# TripleCtrl_v2.net
KiCad netlist of a schematic drawn in EAGLE
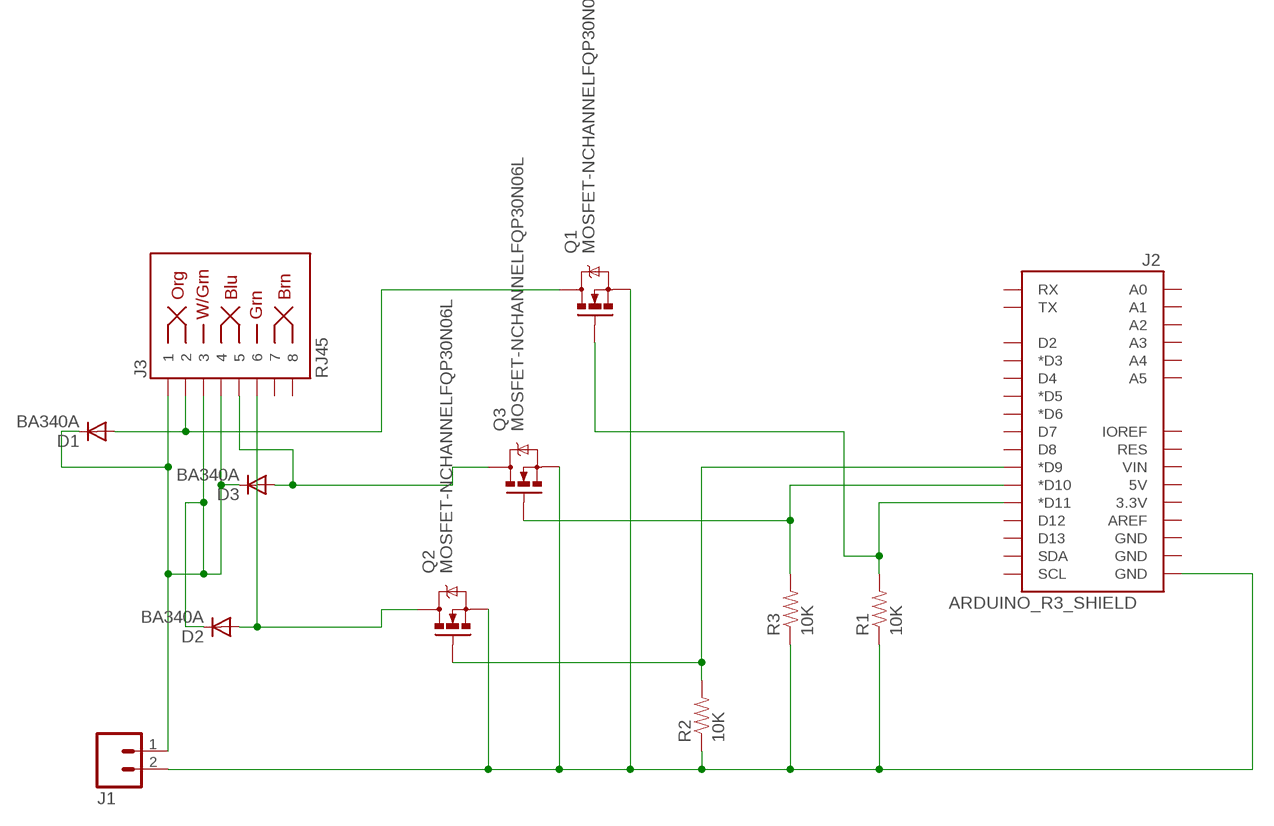
[diagram p0: schematic, sheet 1]

(export (version "E")
  (design (tool "Eeschema 10.0.6"))
  (components
    (comp (ref "D1")
      (value "BA340A")
      (footprint "eagle-import:DO41-10")
      (libsource (lib "eagle-import") (part "1N4004"))
    )
    (comp (ref "D2")
      (value "BA340A")
      (footprint "eagle-import:DO41-10")
      (libsource (lib "eagle-import") (part "1N4004"))
    )
    (comp (ref "D3")
      (value "BA340A")
      (footprint "eagle-import:DO41-10")
      (libsource (lib "eagle-import") (part "1N4004"))
    )
    (comp (ref "J1")
      (value "M025MM")
      (footprint "eagle-import:SCREWTERMINAL-5MM-2")
      (libsource (lib "eagle-import") (part "M025MM"))
    )
    (comp (ref "J2")
      (value "ARDUINO_R3_SHIELD")
      (footprint "eagle-import:UNO_R3_SHIELD")
      (libsource (lib "eagle-import") (part "ARDUINO_R3_SHIELD"))
    )
    (comp (ref "J3")
      (value "RJ45")
      (footprint "eagle-import:RJ45-8")
      (libsource (lib "eagle-import") (part "RJ45-8PTH"))
    )
    (comp (ref "Q1")
      (value "MOSFET-NCHANNELFQP30N06L")
      (footprint "eagle-import:TO220V")
      (libsource (lib "eagle-import") (part "MOSFET-NCHANNELFQP30N06L"))
    )
    (comp (ref "Q2")
      (value "MOSFET-NCHANNELFQP30N06L")
      (footprint "eagle-import:TO220V")
      (libsource (lib "eagle-import") (part "MOSFET-NCHANNELFQP30N06L"))
    )
    (comp (ref "Q3")
      (value "MOSFET-NCHANNELFQP30N06L")
      (footprint "eagle-import:TO220V")
      (libsource (lib "eagle-import") (part "MOSFET-NCHANNELFQP30N06L"))
    )
    (comp (ref "R1")
      (value "10K")
      (footprint "eagle-import:AXIAL-0.3-KIT")
      (libsource (lib "eagle-import") (part "10KOHM-1/6W-5%(PTH)KIT"))
    )
    (comp (ref "R2")
      (value "10K")
      (footprint "eagle-import:AXIAL-0.3-KIT")
      (libsource (lib "eagle-import") (part "10KOHM-1/6W-5%(PTH)KIT"))
    )
    (comp (ref "R3")
      (value "10K")
      (footprint "eagle-import:AXIAL-0.3-KIT")
      (libsource (lib "eagle-import") (part "10KOHM-1/6W-5%(PTH)KIT"))
    )
  )
  (nets
    (net (code "1") (name "Net-(D1-PadC)") (class "Default")
      (node (ref "D1") (pin "C") (pinfunction "C_C") (pintype "passive"))
      (node (ref "D2") (pin "C") (pinfunction "C_C") (pintype "passive"))
      (node (ref "D3") (pin "C") (pinfunction "C_C") (pintype "passive"))
      (node (ref "J1") (pin "1") (pinfunction "1_1") (pintype "passive"))
      (node (ref "J3") (pin "1") (pinfunction "1_1") (pintype "bidirectional"))
      (node (ref "J3") (pin "3") (pinfunction "3_3") (pintype "bidirectional"))
      (node (ref "J3") (pin "4") (pinfunction "4_4") (pintype "bidirectional"))
    )
    (net (code "2") (name "Net-(J2-*D9)") (class "Default")
      (node (ref "J2") (pin "D9") (pinfunction "*D9_D9") (pintype "bidirectional"))
      (node (ref "Q2") (pin "1") (pinfunction "G_1") (pintype "passive"))
      (node (ref "R2") (pin "P$2") (pinfunction "2_P$2") (pintype "passive"))
    )
    (net (code "3") (name "Net-(J2-*D10)") (class "Default")
      (node (ref "J2") (pin "D10") (pinfunction "*D10_D10") (pintype "bidirectional"))
      (node (ref "Q3") (pin "1") (pinfunction "G_1") (pintype "passive"))
      (node (ref "R3") (pin "P$2") (pinfunction "2_P$2") (pintype "passive"))
    )
    (net (code "4") (name "Net-(J2-*D11)") (class "Default")
      (node (ref "J2") (pin "D11") (pinfunction "*D11_D11") (pintype "bidirectional"))
      (node (ref "Q1") (pin "1") (pinfunction "G_1") (pintype "passive"))
      (node (ref "R1") (pin "P$2") (pinfunction "2_P$2") (pintype "passive"))
    )
    (net (code "5") (name "Net-(Q1-D)") (class "Default")
      (node (ref "D1") (pin "A") (pinfunction "A_A") (pintype "passive"))
      (node (ref "J3") (pin "2") (pinfunction "2_2") (pintype "bidirectional"))
      (node (ref "Q1") (pin "2") (pinfunction "D_2") (pintype "passive"))
    )
    (net (code "6") (name "Net-(Q1-S)") (class "Default")
      (node (ref "J1") (pin "2") (pinfunction "2_2") (pintype "passive"))
      (node (ref "J2") (pin "GND@0") (pinfunction "GND_GND@0") (pintype "bidirectional"))
      (node (ref "Q1") (pin "3") (pinfunction "S_3") (pintype "passive"))
      (node (ref "Q2") (pin "3") (pinfunction "S_3") (pintype "passive"))
      (node (ref "Q3") (pin "3") (pinfunction "S_3") (pintype "passive"))
      (node (ref "R1") (pin "P$1") (pinfunction "1_P$1") (pintype "passive"))
      (node (ref "R2") (pin "P$1") (pinfunction "1_P$1") (pintype "passive"))
      (node (ref "R3") (pin "P$1") (pinfunction "1_P$1") (pintype "passive"))
    )
    (net (code "7") (name "Net-(Q2-D)") (class "Default")
      (node (ref "D2") (pin "A") (pinfunction "A_A") (pintype "passive"))
      (node (ref "J3") (pin "6") (pinfunction "6_6") (pintype "bidirectional"))
      (node (ref "Q2") (pin "2") (pinfunction "D_2") (pintype "passive"))
    )
    (net (code "8") (name "Net-(Q3-D)") (class "Default")
      (node (ref "D3") (pin "A") (pinfunction "A_A") (pintype "passive"))
      (node (ref "J3") (pin "5") (pinfunction "5_5") (pintype "bidirectional"))
      (node (ref "Q3") (pin "2") (pinfunction "D_2") (pintype "passive"))
    )
    (net (code "9") (name "unconnected-(J2-*D3-PadD3)") (class "Default")
      (node (ref "J2") (pin "D3") (pinfunction "*D3_D3") (pintype "bidirectional"))
    )
    (net (code "10") (name "unconnected-(J2-*D5-PadD5)") (class "Default")
      (node (ref "J2") (pin "D5") (pinfunction "*D5_D5") (pintype "bidirectional"))
    )
    (net (code "11") (name "unconnected-(J2-*D6-PadD6)") (class "Default")
      (node (ref "J2") (pin "D6") (pinfunction "*D6_D6") (pintype "bidirectional"))
    )
    (net (code "12") (name "unconnected-(J2-GND-PadGND@1)") (class "Default")
      (node (ref "J2") (pin "GND@1") (pinfunction "GND_GND@1") (pintype "bidirectional"))
    )
    (net (code "13") (name "unconnected-(J2-GND-PadGND@2)") (class "Default")
      (node (ref "J2") (pin "GND@2") (pinfunction "GND_GND@2") (pintype "bidirectional"))
    )
    (net (code "14") (name "unconnected-(J2-Pad3.3V)") (class "Default")
      (node (ref "J2") (pin "3.3V") (pinfunction "3.3V_3.3V") (pintype "bidirectional"))
    )
    (net (code "15") (name "unconnected-(J2-Pad5V)") (class "Default")
      (node (ref "J2") (pin "5V") (pinfunction "5V_5V") (pintype "bidirectional"))
    )
    (net (code "16") (name "unconnected-(J2-PadA0)") (class "Default")
      (node (ref "J2") (pin "A0") (pinfunction "A0_A0") (pintype "bidirectional"))
    )
    (net (code "17") (name "unconnected-(J2-PadA1)") (class "Default")
      (node (ref "J2") (pin "A1") (pinfunction "A1_A1") (pintype "bidirectional"))
    )
    (net (code "18") (name "unconnected-(J2-PadA2)") (class "Default")
      (node (ref "J2") (pin "A2") (pinfunction "A2_A2") (pintype "bidirectional"))
    )
    (net (code "19") (name "unconnected-(J2-PadA3)") (class "Default")
      (node (ref "J2") (pin "A3") (pinfunction "A3_A3") (pintype "bidirectional"))
    )
    (net (code "20") (name "unconnected-(J2-PadA4)") (class "Default")
      (node (ref "J2") (pin "A4") (pinfunction "A4_A4") (pintype "bidirectional"))
    )
    (net (code "21") (name "unconnected-(J2-PadA5)") (class "Default")
      (node (ref "J2") (pin "A5") (pinfunction "A5_A5") (pintype "bidirectional"))
    )
    (net (code "22") (name "unconnected-(J2-PadAREF)") (class "Default")
      (node (ref "J2") (pin "AREF") (pinfunction "AREF_AREF") (pintype "bidirectional"))
    )
    (net (code "23") (name "unconnected-(J2-PadD2)") (class "Default")
      (node (ref "J2") (pin "D2") (pinfunction "D2_D2") (pintype "bidirectional"))
    )
    (net (code "24") (name "unconnected-(J2-PadD4)") (class "Default")
      (node (ref "J2") (pin "D4") (pinfunction "D4_D4") (pintype "bidirectional"))
    )
    (net (code "25") (name "unconnected-(J2-PadD7)") (class "Default")
      (node (ref "J2") (pin "D7") (pinfunction "D7_D7") (pintype "bidirectional"))
    )
    (net (code "26") (name "unconnected-(J2-PadD8)") (class "Default")
      (node (ref "J2") (pin "D8") (pinfunction "D8_D8") (pintype "bidirectional"))
    )
    (net (code "27") (name "unconnected-(J2-PadD12)") (class "Default")
      (node (ref "J2") (pin "D12") (pinfunction "D12_D12") (pintype "bidirectional"))
    )
    (net (code "28") (name "unconnected-(J2-PadD13)") (class "Default")
      (node (ref "J2") (pin "D13") (pinfunction "D13_D13") (pintype "bidirectional"))
    )
    (net (code "29") (name "unconnected-(J2-PadIOREF)") (class "Default")
      (node (ref "J2") (pin "IOREF") (pinfunction "IOREF_IOREF") (pintype "bidirectional"))
    )
    (net (code "30") (name "unconnected-(J2-PadRES)") (class "Default")
      (node (ref "J2") (pin "RES") (pinfunction "RES_RES") (pintype "bidirectional"))
    )
    (net (code "31") (name "unconnected-(J2-PadRX)") (class "Default")
      (node (ref "J2") (pin "RX") (pinfunction "RX_RX") (pintype "bidirectional"))
    )
    (net (code "32") (name "unconnected-(J2-PadSCL)") (class "Default")
      (node (ref "J2") (pin "SCL") (pinfunction "SCL_SCL") (pintype "bidirectional"))
    )
    (net (code "33") (name "unconnected-(J2-PadSDA)") (class "Default")
      (node (ref "J2") (pin "SDA") (pinfunction "SDA_SDA") (pintype "bidirectional"))
    )
    (net (code "34") (name "unconnected-(J2-PadTX)") (class "Default")
      (node (ref "J2") (pin "TX") (pinfunction "TX_TX") (pintype "bidirectional"))
    )
    (net (code "35") (name "unconnected-(J2-PadVIN)") (class "Default")
      (node (ref "J2") (pin "VIN") (pinfunction "VIN_VIN") (pintype "bidirectional"))
    )
    (net (code "36") (name "unconnected-(J3-Pad7)") (class "Default")
      (node (ref "J3") (pin "7") (pinfunction "7_7") (pintype "bidirectional"))
    )
    (net (code "37") (name "unconnected-(J3-Pad8)") (class "Default")
      (node (ref "J3") (pin "8") (pinfunction "8_8") (pintype "bidirectional"))
    )
  )
)
